# KW2CPU_PCB.net
KiCad netlist of a schematic drawn in EAGLE
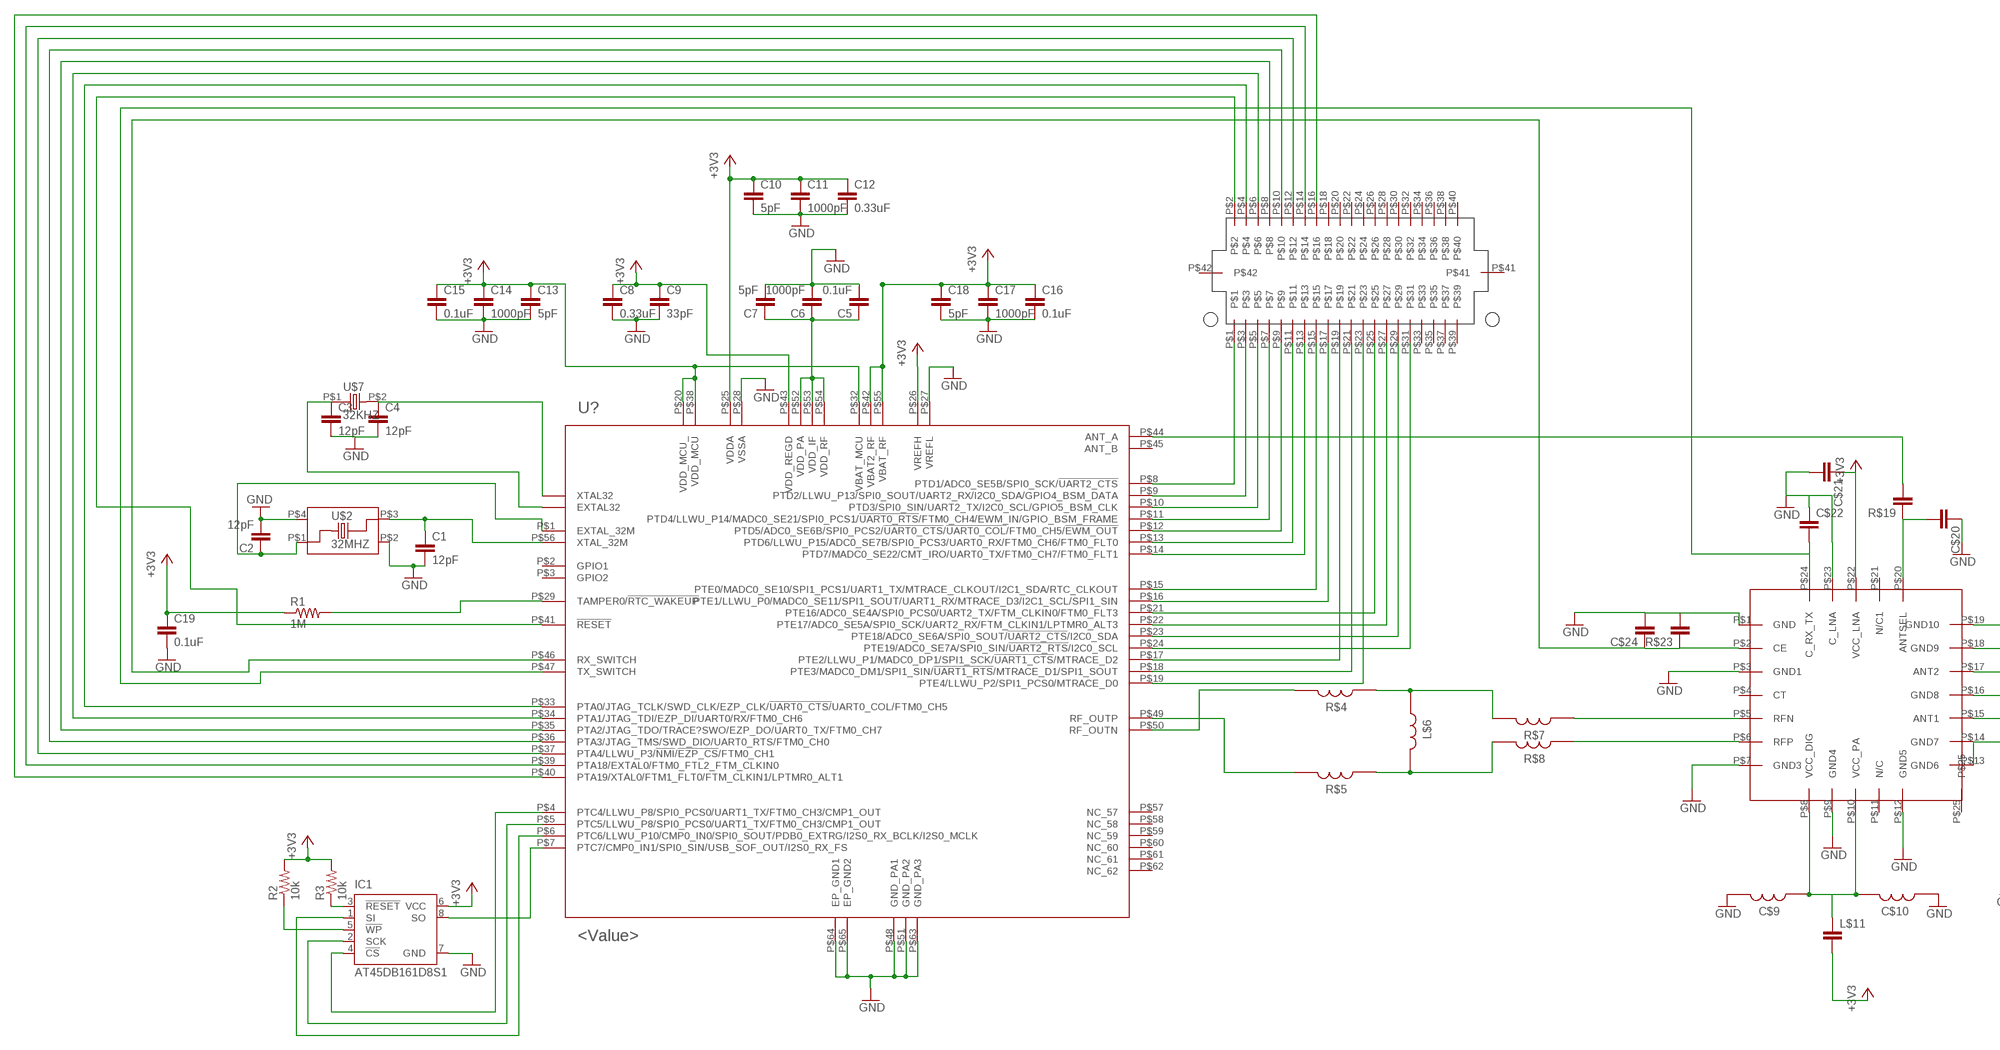
[diagram p0: schematic, sheet 1, part 1 of 2]
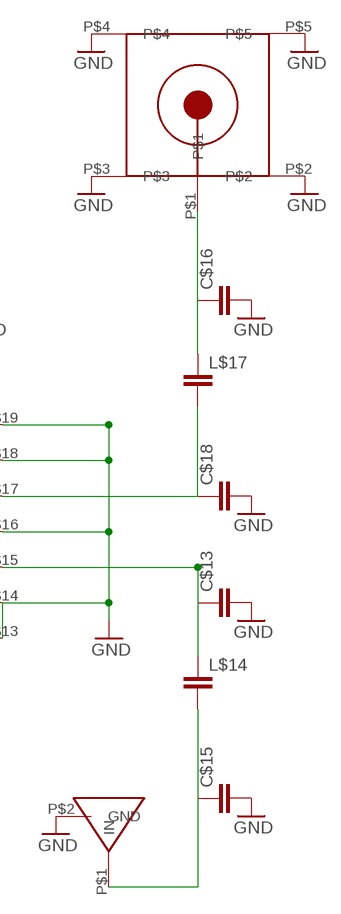
[diagram p1: schematic, sheet 1, part 2 of 2]

(export (version "E")
  (design (tool "Eeschema 10.0.6"))
  (components
    (comp (ref "C$9")
      (value "RF-L")
      (footprint "eagle-import:RF-L0201")
      (libsource (lib "eagle-import") (part "RF-L"))
    )
    (comp (ref "C$10")
      (value "RF-L")
      (footprint "eagle-import:RF-L0201")
      (libsource (lib "eagle-import") (part "RF-L"))
    )
    (comp (ref "C$13")
      (value "RF-C")
      (footprint "eagle-import:RFMD0402")
      (libsource (lib "eagle-import") (part "RF-C"))
    )
    (comp (ref "C$15")
      (value "RF-C")
      (footprint "eagle-import:RFMD0402")
      (libsource (lib "eagle-import") (part "RF-C"))
    )
    (comp (ref "C$16")
      (value "RF-C")
      (footprint "eagle-import:RFMD0402")
      (libsource (lib "eagle-import") (part "RF-C"))
    )
    (comp (ref "C$18")
      (value "RF-C")
      (footprint "eagle-import:RFMD0402")
      (libsource (lib "eagle-import") (part "RF-C"))
    )
    (comp (ref "C$20")
      (value "RF-C")
      (footprint "eagle-import:RFMD0402")
      (libsource (lib "eagle-import") (part "RF-C"))
    )
    (comp (ref "C$21")
      (value "RF-C")
      (footprint "eagle-import:RFMD0402")
      (libsource (lib "eagle-import") (part "RF-C"))
    )
    (comp (ref "C$22")
      (value "RF-C")
      (footprint "eagle-import:RFMD0402")
      (libsource (lib "eagle-import") (part "RF-C"))
    )
    (comp (ref "C$24")
      (value "RF-C")
      (footprint "eagle-import:RFMD0402")
      (libsource (lib "eagle-import") (part "RF-C"))
    )
    (comp (ref "C1")
      (value "12pF")
      (footprint "eagle-import:C0402")
      (libsource (lib "eagle-import") (part "RF-C0402"))
    )
    (comp (ref "C2")
      (value "12pF")
      (footprint "eagle-import:C0402")
      (libsource (lib "eagle-import") (part "RF-C0402"))
    )
    (comp (ref "C3")
      (value "12pF")
      (footprint "eagle-import:C0402")
      (libsource (lib "eagle-import") (part "RF-C0402"))
    )
    (comp (ref "C4")
      (value "12pF")
      (footprint "eagle-import:C0402")
      (libsource (lib "eagle-import") (part "RF-C0402"))
    )
    (comp (ref "C5")
      (value "0.1uF")
      (footprint "eagle-import:C0402")
      (libsource (lib "eagle-import") (part "RF-C0402"))
    )
    (comp (ref "C6")
      (value "1000pF")
      (footprint "eagle-import:C0402")
      (libsource (lib "eagle-import") (part "RF-C0402"))
    )
    (comp (ref "C7")
      (value "5pF")
      (footprint "eagle-import:C0402")
      (libsource (lib "eagle-import") (part "RF-C0402"))
    )
    (comp (ref "C8")
      (value "0.33uF")
      (footprint "eagle-import:C0402")
      (libsource (lib "eagle-import") (part "RF-C0402"))
    )
    (comp (ref "C9")
      (value "33pF")
      (footprint "eagle-import:C0402")
      (libsource (lib "eagle-import") (part "RF-C0402"))
    )
    (comp (ref "C10")
      (value "5pF")
      (footprint "eagle-import:C0402")
      (libsource (lib "eagle-import") (part "RF-C0402"))
    )
    (comp (ref "C11")
      (value "1000pF")
      (footprint "eagle-import:C0402")
      (libsource (lib "eagle-import") (part "RF-C0402"))
    )
    (comp (ref "C12")
      (value "0.33uF")
      (footprint "eagle-import:C0402")
      (libsource (lib "eagle-import") (part "RF-C0402"))
    )
    (comp (ref "C13")
      (value "5pF")
      (footprint "eagle-import:C0402")
      (libsource (lib "eagle-import") (part "RF-C0402"))
    )
    (comp (ref "C14")
      (value "1000pF")
      (footprint "eagle-import:C0402")
      (libsource (lib "eagle-import") (part "RF-C0402"))
    )
    (comp (ref "C15")
      (value "0.1uF")
      (footprint "eagle-import:C0402")
      (libsource (lib "eagle-import") (part "RF-C0402"))
    )
    (comp (ref "C16")
      (value "0.1uF")
      (footprint "eagle-import:C0402")
      (libsource (lib "eagle-import") (part "RF-C0402"))
    )
    (comp (ref "C17")
      (value "1000pF")
      (footprint "eagle-import:C0402")
      (libsource (lib "eagle-import") (part "RF-C0402"))
    )
    (comp (ref "C18")
      (value "5pF")
      (footprint "eagle-import:C0402")
      (libsource (lib "eagle-import") (part "RF-C0402"))
    )
    (comp (ref "C19")
      (value "0.1uF")
      (footprint "eagle-import:C0402")
      (libsource (lib "eagle-import") (part "RF-C0402"))
    )
    (comp (ref "IC1")
      (value "AT45DB161D8S1")
      (footprint "eagle-import:8S1")
      (libsource (lib "eagle-import") (part "AT45DB161D8S1"))
    )
    (comp (ref "L$6")
      (value "RF-L")
      (footprint "eagle-import:RF-L0201")
      (libsource (lib "eagle-import") (part "RF-L"))
    )
    (comp (ref "L$11")
      (value "RF-C")
      (footprint "eagle-import:RFMD0402")
      (libsource (lib "eagle-import") (part "RF-C"))
    )
    (comp (ref "L$14")
      (value "RF-C")
      (footprint "eagle-import:RFMD0402")
      (libsource (lib "eagle-import") (part "RF-C"))
    )
    (comp (ref "L$17")
      (value "RF-C")
      (footprint "eagle-import:RFMD0402")
      (libsource (lib "eagle-import") (part "RF-C"))
    )
    (comp (ref "R$4")
      (value "RF-L")
      (footprint "eagle-import:RF-L0201")
      (libsource (lib "eagle-import") (part "RF-L"))
    )
    (comp (ref "R$5")
      (value "RF-L")
      (footprint "eagle-import:RF-L0201")
      (libsource (lib "eagle-import") (part "RF-L"))
    )
    (comp (ref "R$7")
      (value "RF-L")
      (footprint "eagle-import:RF-L0201")
      (libsource (lib "eagle-import") (part "RF-L"))
    )
    (comp (ref "R$8")
      (value "RF-L")
      (footprint "eagle-import:RF-L0201")
      (libsource (lib "eagle-import") (part "RF-L"))
    )
    (comp (ref "R$19")
      (value "RF-C")
      (footprint "eagle-import:RFMD0402")
      (libsource (lib "eagle-import") (part "RF-C"))
    )
    (comp (ref "R$23")
      (value "RF-C")
      (footprint "eagle-import:RFMD0402")
      (libsource (lib "eagle-import") (part "RF-C"))
    )
    (comp (ref "R1")
      (value "1M")
      (footprint "eagle-import:RF-R0402")
      (libsource (lib "eagle-import") (part "RF-R0402"))
    )
    (comp (ref "R2")
      (value "10k")
      (footprint "eagle-import:RF-R0402")
      (libsource (lib "eagle-import") (part "RF-R0402"))
    )
    (comp (ref "R3")
      (value "10k")
      (footprint "eagle-import:RF-R0402")
      (libsource (lib "eagle-import") (part "RF-R0402"))
    )
    (comp (ref "U$1")
      (value "MKW21D")
      (footprint "eagle-import:LGA63")
      (libsource (lib "eagle-import") (part "MKW21D"))
    )
    (comp (ref "U$2")
      (value "32MHZ")
      (footprint "eagle-import:32MHZSMD")
      (libsource (lib "eagle-import") (part "32MHZ"))
    )
    (comp (ref "U$3")
      (value "RF6555")
      (footprint "eagle-import:RF6555")
      (libsource (lib "eagle-import") (part "RF6555"))
    )
    (comp (ref "U$4")
      (value "F-ANTENNA")
      (footprint "eagle-import:F_ANT_RFMD")
      (libsource (lib "eagle-import") (part "F-ANTENNA"))
    )
    (comp (ref "U$5")
      (value "MMCX_VERT")
      (footprint "eagle-import:MMCX_VERT")
      (libsource (lib "eagle-import") (part "MMCX_VERT"))
    )
    (comp (ref "U$6")
      (value "DF12_M")
      (footprint "eagle-import:DF12_M")
      (libsource (lib "eagle-import") (part "DF12_M"))
    )
    (comp (ref "U$7")
      (value "32KHZ")
      (footprint "eagle-import:32KHZSMD")
      (libsource (lib "eagle-import") (part "32KHZ"))
    )
  )
  (nets
    (net (code "1") (name "+3V3") (class "Default")
      (node (ref "C$21") (pin "P$1") (pinfunction "1_P$1") (pintype "passive"))
      (node (ref "C10") (pin "1") (pinfunction "1_1") (pintype "passive"))
      (node (ref "C11") (pin "1") (pinfunction "1_1") (pintype "passive"))
      (node (ref "C12") (pin "1") (pinfunction "1_1") (pintype "passive"))
      (node (ref "C13") (pin "1") (pinfunction "1_1") (pintype "passive"))
      (node (ref "C14") (pin "1") (pinfunction "1_1") (pintype "passive"))
      (node (ref "C15") (pin "1") (pinfunction "1_1") (pintype "passive"))
      (node (ref "C16") (pin "1") (pinfunction "1_1") (pintype "passive"))
      (node (ref "C17") (pin "1") (pinfunction "1_1") (pintype "passive"))
      (node (ref "C18") (pin "1") (pinfunction "1_1") (pintype "passive"))
      (node (ref "C19") (pin "1") (pinfunction "1_1") (pintype "passive"))
      (node (ref "C8") (pin "1") (pinfunction "1_1") (pintype "passive"))
      (node (ref "C9") (pin "1") (pinfunction "1_1") (pintype "passive"))
      (node (ref "IC1") (pin "6") (pinfunction "VCC_6") (pintype "power_in"))
      (node (ref "L$11") (pin "P$2") (pinfunction "2_P$2") (pintype "passive"))
      (node (ref "R1") (pin "1") (pinfunction "1_1") (pintype "passive"))
      (node (ref "R2") (pin "2") (pinfunction "2_2") (pintype "passive"))
      (node (ref "R3") (pin "2") (pinfunction "2_2") (pintype "passive"))
      (node (ref "U$1") (pin "P$20") (pinfunction "VDD_MCU__P$20") (pintype "bidirectional"))
      (node (ref "U$1") (pin "P$25") (pinfunction "VDDA_P$25") (pintype "bidirectional"))
      (node (ref "U$1") (pin "P$26") (pinfunction "VREFH_P$26") (pintype "bidirectional"))
      (node (ref "U$1") (pin "P$32") (pinfunction "VBAT_MCU_P$32") (pintype "bidirectional"))
      (node (ref "U$1") (pin "P$38") (pinfunction "VDD_MCU_P$38") (pintype "bidirectional"))
      (node (ref "U$1") (pin "P$42") (pinfunction "VBAT2_RF_P$42") (pintype "bidirectional"))
      (node (ref "U$1") (pin "P$43") (pinfunction "VDD_REGD_P$43") (pintype "bidirectional"))
      (node (ref "U$1") (pin "P$55") (pinfunction "VBAT_RF_P$55") (pintype "bidirectional"))
      (node (ref "U$3") (pin "P$22") (pinfunction "VCC_LNA_P$22") (pintype "bidirectional"))
    )
    (net (code "2") (name "GND") (class "Default")
      (node (ref "C$10") (pin "P$2") (pinfunction "2_P$2") (pintype "bidirectional"))
      (node (ref "C$13") (pin "P$2") (pinfunction "2_P$2") (pintype "passive"))
      (node (ref "C$15") (pin "P$2") (pinfunction "2_P$2") (pintype "passive"))
      (node (ref "C$16") (pin "P$2") (pinfunction "2_P$2") (pintype "passive"))
      (node (ref "C$18") (pin "P$2") (pinfunction "2_P$2") (pintype "passive"))
      (node (ref "C$20") (pin "P$1") (pinfunction "1_P$1") (pintype "passive"))
      (node (ref "C$21") (pin "P$2") (pinfunction "2_P$2") (pintype "passive"))
      (node (ref "C$22") (pin "P$1") (pinfunction "1_P$1") (pintype "passive"))
      (node (ref "C$24") (pin "P$2") (pinfunction "2_P$2") (pintype "passive"))
      (node (ref "C$9") (pin "P$1") (pinfunction "1_P$1") (pintype "bidirectional"))
      (node (ref "C1") (pin "2") (pinfunction "2_2") (pintype "passive"))
      (node (ref "C10") (pin "2") (pinfunction "2_2") (pintype "passive"))
      (node (ref "C11") (pin "2") (pinfunction "2_2") (pintype "passive"))
      (node (ref "C12") (pin "2") (pinfunction "2_2") (pintype "passive"))
      (node (ref "C13") (pin "2") (pinfunction "2_2") (pintype "passive"))
      (node (ref "C14") (pin "2") (pinfunction "2_2") (pintype "passive"))
      (node (ref "C15") (pin "2") (pinfunction "2_2") (pintype "passive"))
      (node (ref "C16") (pin "2") (pinfunction "2_2") (pintype "passive"))
      (node (ref "C17") (pin "2") (pinfunction "2_2") (pintype "passive"))
      (node (ref "C18") (pin "2") (pinfunction "2_2") (pintype "passive"))
      (node (ref "C19") (pin "2") (pinfunction "2_2") (pintype "passive"))
      (node (ref "C2") (pin "2") (pinfunction "2_2") (pintype "passive"))
      (node (ref "C3") (pin "2") (pinfunction "2_2") (pintype "passive"))
      (node (ref "C4") (pin "2") (pinfunction "2_2") (pintype "passive"))
      (node (ref "C5") (pin "2") (pinfunction "2_2") (pintype "passive"))
      (node (ref "C6") (pin "2") (pinfunction "2_2") (pintype "passive"))
      (node (ref "C7") (pin "2") (pinfunction "2_2") (pintype "passive"))
      (node (ref "C8") (pin "2") (pinfunction "2_2") (pintype "passive"))
      (node (ref "C9") (pin "2") (pinfunction "2_2") (pintype "passive"))
      (node (ref "IC1") (pin "7") (pinfunction "GND_7") (pintype "power_in"))
      (node (ref "U$1") (pin "P$27") (pinfunction "VREFL_P$27") (pintype "bidirectional"))
      (node (ref "U$1") (pin "P$28") (pinfunction "VSSA_P$28") (pintype "bidirectional"))
      (node (ref "U$1") (pin "P$48") (pinfunction "GND_PA1_P$48") (pintype "bidirectional"))
      (node (ref "U$1") (pin "P$51") (pinfunction "GND_PA2_P$51") (pintype "bidirectional"))
      (node (ref "U$1") (pin "P$63") (pinfunction "GND_PA3_P$63") (pintype "bidirectional"))
      (node (ref "U$1") (pin "P$64") (pinfunction "EP_GND1_P$64") (pintype "bidirectional"))
      (node (ref "U$1") (pin "P$65") (pinfunction "EP_GND2_P$65") (pintype "bidirectional"))
      (node (ref "U$2") (pin "P$2") (pinfunction "P$2_P$2") (pintype "power_in"))
      (node (ref "U$2") (pin "P$4") (pinfunction "P$4_P$4") (pintype "bidirectional"))
      (node (ref "U$3") (pin "P$1") (pinfunction "GND_P$1") (pintype "bidirectional"))
      (node (ref "U$3") (pin "P$12") (pinfunction "GND5_P$12") (pintype "bidirectional"))
      (node (ref "U$3") (pin "P$13") (pinfunction "GND6_P$13") (pintype "bidirectional"))
      (node (ref "U$3") (pin "P$14") (pinfunction "GND7_P$14") (pintype "bidirectional"))
      (node (ref "U$3") (pin "P$16") (pinfunction "GND8_P$16") (pintype "bidirectional"))
      (node (ref "U$3") (pin "P$18") (pinfunction "GND9_P$18") (pintype "bidirectional"))
      (node (ref "U$3") (pin "P$19") (pinfunction "GND10_P$19") (pintype "bidirectional"))
      (node (ref "U$3") (pin "P$23") (pinfunction "C_LNA_P$23") (pintype "bidirectional"))
      (node (ref "U$3") (pin "P$3") (pinfunction "GND1_P$3") (pintype "bidirectional"))
      (node (ref "U$3") (pin "P$7") (pinfunction "GND3_P$7") (pintype "bidirectional"))
      (node (ref "U$3") (pin "P$9") (pinfunction "GND4_P$9") (pintype "bidirectional"))
      (node (ref "U$4") (pin "P$2") (pinfunction "GND_P$2") (pintype "bidirectional"))
      (node (ref "U$5") (pin "P$2") (pinfunction "P$2_P$2") (pintype "bidirectional"))
      (node (ref "U$5") (pin "P$3") (pinfunction "P$3_P$3") (pintype "bidirectional"))
      (node (ref "U$5") (pin "P$4") (pinfunction "P$4_P$4") (pintype "bidirectional"))
      (node (ref "U$5") (pin "P$5") (pinfunction "P$5_P$5") (pintype "bidirectional"))
    )
    (net (code "3") (name "Net-(C$10-1)") (class "Default")
      (node (ref "C$10") (pin "P$1") (pinfunction "1_P$1") (pintype "bidirectional"))
      (node (ref "C$9") (pin "P$2") (pinfunction "2_P$2") (pintype "bidirectional"))
      (node (ref "L$11") (pin "P$1") (pinfunction "1_P$1") (pintype "passive"))
      (node (ref "U$3") (pin "P$10") (pinfunction "VCC_PA_P$10") (pintype "bidirectional"))
      (node (ref "U$3") (pin "P$8") (pinfunction "VCC_DIG_P$8") (pintype "bidirectional"))
    )
    (net (code "4") (name "Net-(C$13-1)") (class "Default")
      (node (ref "C$13") (pin "P$1") (pinfunction "1_P$1") (pintype "passive"))
      (node (ref "L$14") (pin "P$1") (pinfunction "1_P$1") (pintype "passive"))
      (node (ref "U$3") (pin "P$15") (pinfunction "ANT1_P$15") (pintype "bidirectional"))
    )
    (net (code "5") (name "Net-(C$15-1)") (class "Default")
      (node (ref "C$15") (pin "P$1") (pinfunction "1_P$1") (pintype "passive"))
      (node (ref "L$14") (pin "P$2") (pinfunction "2_P$2") (pintype "passive"))
      (node (ref "U$4") (pin "P$1") (pinfunction "IN_P$1") (pintype "bidirectional"))
    )
    (net (code "6") (name "Net-(C$16-1)") (class "Default")
      (node (ref "C$16") (pin "P$1") (pinfunction "1_P$1") (pintype "passive"))
      (node (ref "L$17") (pin "P$1") (pinfunction "1_P$1") (pintype "passive"))
      (node (ref "U$5") (pin "P$1") (pinfunction "P$1_P$1") (pintype "bidirectional"))
    )
    (net (code "7") (name "Net-(C$18-1)") (class "Default")
      (node (ref "C$18") (pin "P$1") (pinfunction "1_P$1") (pintype "passive"))
      (node (ref "L$17") (pin "P$2") (pinfunction "2_P$2") (pintype "passive"))
      (node (ref "U$3") (pin "P$17") (pinfunction "ANT2_P$17") (pintype "bidirectional"))
    )
    (net (code "8") (name "Net-(C$20-2)") (class "Default")
      (node (ref "C$20") (pin "P$2") (pinfunction "2_P$2") (pintype "passive"))
      (node (ref "R$19") (pin "P$1") (pinfunction "1_P$1") (pintype "passive"))
      (node (ref "U$3") (pin "P$20") (pinfunction "ANTSEL_P$20") (pintype "bidirectional"))
    )
    (net (code "9") (name "Net-(C$22-2)") (class "Default")
      (node (ref "C$22") (pin "P$2") (pinfunction "2_P$2") (pintype "passive"))
      (node (ref "U$1") (pin "P$47") (pinfunction "TX_SWITCH_P$47") (pintype "bidirectional"))
      (node (ref "U$3") (pin "P$24") (pinfunction "C_RX_TX_P$24") (pintype "bidirectional"))
    )
    (net (code "10") (name "Net-(C$24-1)") (class "Default")
      (node (ref "C$24") (pin "P$1") (pinfunction "1_P$1") (pintype "passive"))
      (node (ref "R$23") (pin "P$1") (pinfunction "1_P$1") (pintype "passive"))
      (node (ref "U$1") (pin "P$46") (pinfunction "RX_SWITCH_P$46") (pintype "bidirectional"))
      (node (ref "U$3") (pin "P$2") (pinfunction "CE_P$2") (pintype "bidirectional"))
    )
    (net (code "11") (name "Net-(IC1-SCK)") (class "Default")
      (node (ref "IC1") (pin "2") (pinfunction "SCK_2") (pintype "input"))
      (node (ref "U$1") (pin "P$5") (pinfunction "PTC5/LLWU_P8/SPI0_PCS0/UART1_TX/FTM0_CH3/CMP1_OUT_P$5") (pintype "bidirectional"))
    )
    (net (code "12") (name "Net-(IC1-SI)") (class "Default")
      (node (ref "IC1") (pin "1") (pinfunction "SI_1") (pintype "input"))
      (node (ref "U$1") (pin "P$6") (pinfunction "PTC6/LLWU_P10/CMP0_IN0/SPI0_SOUT/PDB0_EXTRG/I2S0_RX_BCLK/I2S0_MCLK_P$6") (pintype "bidirectional"))
    )
    (net (code "13") (name "Net-(IC1-SO)") (class "Default")
      (node (ref "IC1") (pin "8") (pinfunction "SO_8") (pintype "output"))
      (node (ref "U$1") (pin "P$7") (pinfunction "PTC7/CMP0_IN1/SPI0_SIN/USB_SOF_OUT/I2S0_RX_FS_P$7") (pintype "bidirectional"))
    )
    (net (code "14") (name "Net-(IC1-~{CS})") (class "Default")
      (node (ref "IC1") (pin "4") (pinfunction "~{CS}_4") (pintype "input"))
      (node (ref "U$1") (pin "P$4") (pinfunction "PTC4/LLWU_P8/SPI0_PCS0/UART1_TX/FTM0_CH3/CMP1_OUT_P$4") (pintype "bidirectional"))
    )
    (net (code "15") (name "Net-(IC1-~{RESET})") (class "Default")
      (node (ref "IC1") (pin "3") (pinfunction "~{RESET}_3") (pintype "input"))
      (node (ref "R3") (pin "1") (pinfunction "1_1") (pintype "passive"))
    )
    (net (code "16") (name "Net-(IC1-~{WP})") (class "Default")
      (node (ref "IC1") (pin "5") (pinfunction "~{WP}_5") (pintype "input"))
      (node (ref "R2") (pin "1") (pinfunction "1_1") (pintype "passive"))
    )
    (net (code "17") (name "Net-(L$6-1)") (class "Default")
      (node (ref "L$6") (pin "P$1") (pinfunction "1_P$1") (pintype "bidirectional"))
      (node (ref "R$5") (pin "P$2") (pinfunction "2_P$2") (pintype "bidirectional"))
      (node (ref "R$8") (pin "P$1") (pinfunction "1_P$1") (pintype "bidirectional"))
    )
    (net (code "18") (name "Net-(L$6-2)") (class "Default")
      (node (ref "L$6") (pin "P$2") (pinfunction "2_P$2") (pintype "bidirectional"))
      (node (ref "R$4") (pin "P$2") (pinfunction "2_P$2") (pintype "bidirectional"))
      (node (ref "R$7") (pin "P$1") (pinfunction "1_P$1") (pintype "bidirectional"))
    )
    (net (code "19") (name "Net-(R$4-1)") (class "Default")
      (node (ref "R$4") (pin "P$1") (pinfunction "1_P$1") (pintype "bidirectional"))
      (node (ref "U$1") (pin "P$50") (pinfunction "RF_OUTN_P$50") (pintype "bidirectional"))
    )
    (net (code "20") (name "Net-(R$5-1)") (class "Default")
      (node (ref "R$5") (pin "P$1") (pinfunction "1_P$1") (pintype "bidirectional"))
      (node (ref "U$1") (pin "P$49") (pinfunction "RF_OUTP_P$49") (pintype "bidirectional"))
    )
    (net (code "21") (name "Net-(R$7-2)") (class "Default")
      (node (ref "R$7") (pin "P$2") (pinfunction "2_P$2") (pintype "bidirectional"))
      (node (ref "U$3") (pin "P$5") (pinfunction "RFN_P$5") (pintype "bidirectional"))
    )
    (net (code "22") (name "Net-(R$8-2)") (class "Default")
      (node (ref "R$8") (pin "P$2") (pinfunction "2_P$2") (pintype "bidirectional"))
      (node (ref "U$3") (pin "P$6") (pinfunction "RFP_P$6") (pintype "bidirectional"))
    )
    (net (code "23") (name "Net-(R$19-2)") (class "Default")
      (node (ref "R$19") (pin "P$2") (pinfunction "2_P$2") (pintype "passive"))
      (node (ref "U$1") (pin "P$44") (pinfunction "ANT_A_P$44") (pintype "bidirectional"))
    )
    (net (code "24") (name "Net-(U$1-EXTAL32)") (class "Default")
      (node (ref "C3") (pin "1") (pinfunction "1_1") (pintype "passive"))
      (node (ref "U$1") (pin "P$31") (pinfunction "EXTAL32_P$31") (pintype "bidirectional"))
      (node (ref "U$7") (pin "P$1") (pinfunction "1_P$1") (pintype "passive"))
    )
    (net (code "25") (name "Net-(U$1-EXTAL_32M)") (class "Default")
      (node (ref "C2") (pin "1") (pinfunction "1_1") (pintype "passive"))
      (node (ref "U$1") (pin "P$1") (pinfunction "EXTAL_32M_P$1") (pintype "bidirectional"))
      (node (ref "U$2") (pin "P$1") (pinfunction "P$1_P$1") (pintype "passive"))
    )
    (net (code "26") (name "Net-(U$1-PTA0{slash}JTAG_TCLK{slash}SWD_CLK{slash}EZP_CLK{slash}~{UART0_CTS{slash}}UART0_COL{slash}FTM0_CH5)") (class "Default")
      (node (ref "U$1") (pin "P$33") (pinfunction "PTA0/JTAG_TCLK/SWD_CLK/EZP_CLK/~{UART0_CTS/}UART0_COL/FTM0_CH5_P$33") (pintype "bidirectional"))
      (node (ref "U$6") (pin "P$4") (pinfunction "P$4_P$4") (pintype "bidirectional"))
    )
    (net (code "27") (name "Net-(U$1-PTA1{slash}JTAG_TDI{slash}EZP_DI{slash}UART0{slash}RX{slash}FTM0_CH6)") (class "Default")
      (node (ref "U$1") (pin "P$34") (pinfunction "PTA1/JTAG_TDI/EZP_DI/UART0/RX/FTM0_CH6_P$34") (pintype "bidirectional"))
      (node (ref "U$6") (pin "P$6") (pinfunction "P$6_P$6") (pintype "bidirectional"))
    )
    (net (code "28") (name "Net-(U$1-PTA2{slash}JTAG_TDO{slash}TRACE?SWO{slash}EZP_DO{slash}UART0_TX{slash}FTM0_CH7)") (class "Default")
      (node (ref "U$1") (pin "P$35") (pinfunction "PTA2/JTAG_TDO/TRACE?SWO/EZP_DO/UART0_TX/FTM0_CH7_P$35") (pintype "bidirectional"))
      (node (ref "U$6") (pin "P$8") (pinfunction "P$8_P$8") (pintype "bidirectional"))
    )
    (net (code "29") (name "Net-(U$1-PTA3{slash}JTAG_TMS{slash}SWD_DIO{slash}UART0_RTS{slash}FTM0_CH0)") (class "Default")
      (node (ref "U$1") (pin "P$36") (pinfunction "PTA3/JTAG_TMS/SWD_DIO/UART0_RTS/FTM0_CH0_P$36") (pintype "bidirectional"))
      (node (ref "U$6") (pin "P$10") (pinfunction "P$10_P$10") (pintype "bidirectional"))
    )
    (net (code "30") (name "Net-(U$1-PTA4{slash}LLWU_P3{slash}~{NMI}{slash}~{EZP_CS}{slash}FTM0_CH1)") (class "Default")
      (node (ref "U$1") (pin "P$37") (pinfunction "PTA4/LLWU_P3/~{NMI}/~{EZP_CS}/FTM0_CH1_P$37") (pintype "bidirectional"))
      (node (ref "U$6") (pin "P$12") (pinfunction "P$12_P$12") (pintype "bidirectional"))
    )
    (net (code "31") (name "Net-(U$1-PTA18{slash}EXTAL0{slash}FTM0_FTL2_FTM_CLKIN0)") (class "Default")
      (node (ref "U$1") (pin "P$39") (pinfunction "PTA18/EXTAL0/FTM0_FTL2_FTM_CLKIN0_P$39") (pintype "bidirectional"))
      (node (ref "U$6") (pin "P$14") (pinfunction "P$14_P$14") (pintype "bidirectional"))
    )
    (net (code "32") (name "Net-(U$1-PTA19{slash}XTAL0{slash}FTM1_FLT0{slash}FTM_CLKIN1{slash}LPTMR0_ALT1)") (class "Default")
      (node (ref "U$1") (pin "P$40") (pinfunction "PTA19/XTAL0/FTM1_FLT0/FTM_CLKIN1/LPTMR0_ALT1_P$40") (pintype "bidirectional"))
      (node (ref "U$6") (pin "P$16") (pinfunction "P$16_P$16") (pintype "bidirectional"))
    )
    (net (code "33") (name "Net-(U$1-PTD1{slash}ADC0_SE5B{slash}SPI0_SCK{slash}~{UART2_CTS})") (class "Default")
      (node (ref "U$1") (pin "P$8") (pinfunction "PTD1/ADC0_SE5B/SPI0_SCK/~{UART2_CTS}_P$8") (pintype "bidirectional"))
      (node (ref "U$6") (pin "P$1") (pinfunction "P$1_P$1") (pintype "bidirectional"))
    )
    (net (code "34") (name "Net-(U$1-PTD2{slash}LLWU_P13{slash}SPI0_SOUT{slash}UART2_RX{slash}I2C0_SDA{slash}GPIO4_BSM_DATA)") (class "Default")
      (node (ref "U$1") (pin "P$9") (pinfunction "PTD2/LLWU_P13/SPI0_SOUT/UART2_RX/I2C0_SDA/GPIO4_BSM_DATA_P$9") (pintype "bidirectional"))
      (node (ref "U$6") (pin "P$3") (pinfunction "P$3_P$3") (pintype "bidirectional"))
    )
    (net (code "35") (name "Net-(U$1-PTD3{slash}SPI0_SIN{slash}UART2_TX{slash}I2C0_SCL{slash}GPIO5_BSM_CLK)") (class "Default")
      (node (ref "U$1") (pin "P$10") (pinfunction "PTD3/SPI0_SIN/UART2_TX/I2C0_SCL/GPIO5_BSM_CLK_P$10") (pintype "bidirectional"))
      (node (ref "U$6") (pin "P$5") (pinfunction "P$5_P$5") (pintype "bidirectional"))
    )
    (net (code "36") (name "Net-(U$1-PTD4{slash}LLWU_P14{slash}MADC0_SE21{slash}SPI0_PCS1{slash}~{UART0_RTS}{slash}FTM0_CH4{slash}EWM_IN{slash}GPIO_BSM_FRAME)") (class "Default")
      (node (ref "U$1") (pin "P$11") (pinfunction "PTD4/LLWU_P14/MADC0_SE21/SPI0_PCS1/~{UART0_RTS}/FTM0_CH4/EWM_IN/GPIO_BSM_FRAME_P$11") (pintype "bidirectional"))
      (node (ref "U$6") (pin "P$7") (pinfunction "P$7_P$7") (pintype "bidirectional"))
    )
    (net (code "37") (name "Net-(U$1-PTD5{slash}ADC0_SE6B{slash}SPI0_PCS2{slash}~{UART0_CTS}{slash}~{UART0_COL}{slash}FTM0_CH5{slash}~{EWM_OUT})") (class "Default")
      (node (ref "U$1") (pin "P$12") (pinfunction "PTD5/ADC0_SE6B/SPI0_PCS2/~{UART0_CTS}/~{UART0_COL}/FTM0_CH5/~{EWM_OUT}_P$12") (pintype "bidirectional"))
      (node (ref "U$6") (pin "P$9") (pinfunction "P$9_P$9") (pintype "bidirectional"))
    )
    (net (code "38") (name "Net-(U$1-PTD6{slash}LLWU_P15{slash}ADC0_SE7B{slash}SPI0_PCS3{slash}UART0_RX{slash}FTM0_CH6{slash}FTM0_FLT0)") (class "Default")
      (node (ref "U$1") (pin "P$13") (pinfunction "PTD6/LLWU_P15/ADC0_SE7B/SPI0_PCS3/UART0_RX/FTM0_CH6/FTM0_FLT0_P$13") (pintype "bidirectional"))
      (node (ref "U$6") (pin "P$11") (pinfunction "P$11_P$11") (pintype "bidirectional"))
    )
    (net (code "39") (name "Net-(U$1-PTD7{slash}MADC0_SE22{slash}CMT_IRO{slash}UART0_TX{slash}FTM0_CH7{slash}FTM0_FLT1)") (class "Default")
      (node (ref "U$1") (pin "P$14") (pinfunction "PTD7/MADC0_SE22/CMT_IRO/UART0_TX/FTM0_CH7/FTM0_FLT1_P$14") (pintype "bidirectional"))
      (node (ref "U$6") (pin "P$13") (pinfunction "P$13_P$13") (pintype "bidirectional"))
    )
    (net (code "40") (name "Net-(U$1-PTE0{slash}MADC0_SE10{slash}SPI1_PCS1{slash}UART1_TX{slash}MTRACE_CLKOUT{slash}I2C1_SDA{slash}RTC_CLKOUT)") (class "Default")
      (node (ref "U$1") (pin "P$15") (pinfunction "PTE0/MADC0_SE10/SPI1_PCS1/UART1_TX/MTRACE_CLKOUT/I2C1_SDA/RTC_CLKOUT_P$15") (pintype "bidirectional"))
      (node (ref "U$6") (pin "P$15") (pinfunction "P$15_P$15") (pintype "bidirectional"))
    )
    (net (code "41") (name "Net-(U$1-PTE1{slash}LLWU_P0{slash}MADC0_SE11{slash}SPI1_SOUT{slash}UART1_RX{slash}MTRACE_D3{slash}I2C1_SCL{slash}SPI1_SIN)") (class "Default")
      (node (ref "U$1") (pin "P$16") (pinfunction "PTE1/LLWU_P0/MADC0_SE11/SPI1_SOUT/UART1_RX/MTRACE_D3/I2C1_SCL/SPI1_SIN_P$16") (pintype "bidirectional"))
      (node (ref "U$6") (pin "P$17") (pinfunction "P$17_P$17") (pintype "bidirectional"))
    )
    (net (code "42") (name "Net-(U$1-PTE2{slash}LLWU_P1{slash}MADC0_DP1{slash}SPI1_SCK{slash}~{UART1_CTS}{slash}MTRACE_D2)") (class "Default")
      (node (ref "U$1") (pin "P$17") (pinfunction "PTE2/LLWU_P1/MADC0_DP1/SPI1_SCK/~{UART1_CTS}/MTRACE_D2_P$17") (pintype "bidirectional"))
      (node (ref "U$6") (pin "P$19") (pinfunction "P$19_P$19") (pintype "bidirectional"))
    )
    (net (code "43") (name "Net-(U$1-PTE3{slash}MADC0_DM1{slash}SPI1_SIN{slash}~{UART1_RTS}{slash}MTRACE_D1{slash}SPI1_SOUT)") (class "Default")
      (node (ref "U$1") (pin "P$18") (pinfunction "PTE3/MADC0_DM1/SPI1_SIN/~{UART1_RTS}/MTRACE_D1/SPI1_SOUT_P$18") (pintype "bidirectional"))
      (node (ref "U$6") (pin "P$21") (pinfunction "P$21_P$21") (pintype "bidirectional"))
    )
    (net (code "44") (name "Net-(U$1-PTE4{slash}LLWU_P2{slash}SPI1_PCS0{slash}MTRACE_D0)") (class "Default")
      (node (ref "U$1") (pin "P$19") (pinfunction "PTE4/LLWU_P2/SPI1_PCS0/MTRACE_D0_P$19") (pintype "bidirectional"))
      (node (ref "U$6") (pin "P$23") (pinfunction "P$23_P$23") (pintype "bidirectional"))
    )
    (net (code "45") (name "Net-(U$1-PTE16{slash}ADC0_SE4A{slash}SPI0_PCS0{slash}UART2_TX{slash}FTM_CLKIN0{slash}FTM0_FLT3)") (class "Default")
      (node (ref "U$1") (pin "P$21") (pinfunction "PTE16/ADC0_SE4A/SPI0_PCS0/UART2_TX/FTM_CLKIN0/FTM0_FLT3_P$21") (pintype "bidirectional"))
      (node (ref "U$6") (pin "P$25") (pinfunction "P$25_P$25") (pintype "bidirectional"))
    )
    (net (code "46") (name "Net-(U$1-PTE17{slash}ADC0_SE5A{slash}SPI0_SCK{slash}UART2_RX{slash}FTM_CLKIN1{slash}LPTMR0_ALT3)") (class "Default")
      (node (ref "U$1") (pin "P$22") (pinfunction "PTE17/ADC0_SE5A/SPI0_SCK/UART2_RX/FTM_CLKIN1/LPTMR0_ALT3_P$22") (pintype "bidirectional"))
      (node (ref "U$6") (pin "P$27") (pinfunction "P$27_P$27") (pintype "bidirectional"))
    )
    (net (code "47") (name "Net-(U$1-PTE18{slash}ADC0_SE6A{slash}SPI0_SOUT{slash}~{UART2_CTS}{slash}I2C0_SDA)") (class "Default")
      (node (ref "U$1") (pin "P$23") (pinfunction "PTE18/ADC0_SE6A/SPI0_SOUT/~{UART2_CTS}/I2C0_SDA_P$23") (pintype "bidirectional"))
      (node (ref "U$6") (pin "P$29") (pinfunction "P$29_P$29") (pintype "bidirectional"))
    )
    (net (code "48") (name "Net-(U$1-PTE19{slash}ADC0_SE7A{slash}SPI0_SIN{slash}~{UART2_RTS}{slash}I2C0_SCL)") (class "Default")
      (node (ref "U$1") (pin "P$24") (pinfunction "PTE19/ADC0_SE7A/SPI0_SIN/~{UART2_RTS}/I2C0_SCL_P$24") (pintype "bidirectional"))
      (node (ref "U$6") (pin "P$31") (pinfunction "P$31_P$31") (pintype "bidirectional"))
    )
    (net (code "49") (name "Net-(U$1-TAMPER0{slash}~{RTC_WAKEUP})") (class "Default")
      (node (ref "R1") (pin "2") (pinfunction "2_2") (pintype "passive"))
      (node (ref "U$1") (pin "P$29") (pinfunction "TAMPER0/~{RTC_WAKEUP}_P$29") (pintype "bidirectional"))
    )
    (net (code "50") (name "Net-(U$1-VDD_IF)") (class "Default")
      (node (ref "C5") (pin "1") (pinfunction "1_1") (pintype "passive"))
      (node (ref "C6") (pin "1") (pinfunction "1_1") (pintype "passive"))
      (node (ref "C7") (pin "1") (pinfunction "1_1") (pintype "passive"))
      (node (ref "U$1") (pin "P$52") (pinfunction "VDD_PA_P$52") (pintype "bidirectional"))
      (node (ref "U$1") (pin "P$53") (pinfunction "VDD_IF_P$53") (pintype "bidirectional"))
      (node (ref "U$1") (pin "P$54") (pinfunction "VDD_RF_P$54") (pintype "bidirectional"))
    )
    (net (code "51") (name "Net-(U$1-XTAL32)") (class "Default")
      (node (ref "C4") (pin "1") (pinfunction "1_1") (pintype "passive"))
      (node (ref "U$1") (pin "P$30") (pinfunction "XTAL32_P$30") (pintype "bidirectional"))
      (node (ref "U$7") (pin "P$2") (pinfunction "2_P$2") (pintype "passive"))
    )
    (net (code "52") (name "Net-(U$1-XTAL_32M)") (class "Default")
      (node (ref "C1") (pin "1") (pinfunction "1_1") (pintype "passive"))
      (node (ref "U$1") (pin "P$56") (pinfunction "XTAL_32M_P$56") (pintype "bidirectional"))
      (node (ref "U$2") (pin "P$3") (pinfunction "P$3_P$3") (pintype "passive"))
    )
    (net (code "53") (name "Net-(U$1-~{RESET})") (class "Default")
      (node (ref "U$1") (pin "P$41") (pinfunction "~{RESET}_P$41") (pintype "bidirectional"))
      (node (ref "U$6") (pin "P$2") (pinfunction "P$2_P$2") (pintype "bidirectional"))
    )
    (net (code "54") (name "unconnected-(R$23-2-PadP$2)") (class "Default")
      (node (ref "R$23") (pin "P$2") (pinfunction "2_P$2") (pintype "passive"))
    )
    (net (code "55") (name "unconnected-(U$1-ANT_B-PadP$45)") (class "Default")
      (node (ref "U$1") (pin "P$45") (pinfunction "ANT_B_P$45") (pintype "bidirectional"))
    )
    (net (code "56") (name "unconnected-(U$1-GPIO1-PadP$2)") (class "Default")
      (node (ref "U$1") (pin "P$2") (pinfunction "GPIO1_P$2") (pintype "bidirectional"))
    )
    (net (code "57") (name "unconnected-(U$1-GPIO2-PadP$3)") (class "Default")
      (node (ref "U$1") (pin "P$3") (pinfunction "GPIO2_P$3") (pintype "bidirectional"))
    )
    (net (code "58") (name "unconnected-(U$1-NC_57-PadP$57)") (class "Default")
      (node (ref "U$1") (pin "P$57") (pinfunction "NC_57_P$57") (pintype "bidirectional"))
    )
    (net (code "59") (name "unconnected-(U$1-NC_58-PadP$58)") (class "Default")
      (node (ref "U$1") (pin "P$58") (pinfunction "NC_58_P$58") (pintype "bidirectional"))
    )
    (net (code "60") (name "unconnected-(U$1-NC_59-PadP$59)") (class "Default")
      (node (ref "U$1") (pin "P$59") (pinfunction "NC_59_P$59") (pintype "bidirectional"))
    )
    (net (code "61") (name "unconnected-(U$1-NC_60-PadP$60)") (class "Default")
      (node (ref "U$1") (pin "P$60") (pinfunction "NC_60_P$60") (pintype "bidirectional"))
    )
    (net (code "62") (name "unconnected-(U$1-NC_61-PadP$61)") (class "Default")
      (node (ref "U$1") (pin "P$61") (pinfunction "NC_61_P$61") (pintype "bidirectional"))
    )
    (net (code "63") (name "unconnected-(U$1-NC_62-PadP$62)") (class "Default")
      (node (ref "U$1") (pin "P$62") (pinfunction "NC_62_P$62") (pintype "bidirectional"))
    )
    (net (code "64") (name "unconnected-(U$3-CT-PadP$4)") (class "Default")
      (node (ref "U$3") (pin "P$4") (pinfunction "CT_P$4") (pintype "bidirectional"))
    )
    (net (code "65") (name "unconnected-(U$3-N{slash}C-PadP$11)") (class "Default")
      (node (ref "U$3") (pin "P$11") (pinfunction "N/C_P$11") (pintype "bidirectional"))
    )
    (net (code "66") (name "unconnected-(U$3-N{slash}C1-PadP$21)") (class "Default")
      (node (ref "U$3") (pin "P$21") (pinfunction "N/C1_P$21") (pintype "bidirectional"))
    )
    (net (code "67") (name "unconnected-(U$3-PadP$25)") (class "Default")
      (node (ref "U$3") (pin "P$25") (pinfunction "P$25_P$25") (pintype "bidirectional"))
    )
    (net (code "68") (name "unconnected-(U$6-PadP$18)") (class "Default")
      (node (ref "U$6") (pin "P$18") (pinfunction "P$18_P$18") (pintype "bidirectional"))
    )
    (net (code "69") (name "unconnected-(U$6-PadP$20)") (class "Default")
      (node (ref "U$6") (pin "P$20") (pinfunction "P$20_P$20") (pintype "bidirectional"))
    )
    (net (code "70") (name "unconnected-(U$6-PadP$22)") (class "Default")
      (node (ref "U$6") (pin "P$22") (pinfunction "P$22_P$22") (pintype "bidirectional"))
    )
    (net (code "71") (name "unconnected-(U$6-PadP$24)") (class "Default")
      (node (ref "U$6") (pin "P$24") (pinfunction "P$24_P$24") (pintype "bidirectional"))
    )
    (net (code "72") (name "unconnected-(U$6-PadP$26)") (class "Default")
      (node (ref "U$6") (pin "P$26") (pinfunction "P$26_P$26") (pintype "bidirectional"))
    )
    (net (code "73") (name "unconnected-(U$6-PadP$28)") (class "Default")
      (node (ref "U$6") (pin "P$28") (pinfunction "P$28_P$28") (pintype "bidirectional"))
    )
    (net (code "74") (name "unconnected-(U$6-PadP$30)") (class "Default")
      (node (ref "U$6") (pin "P$30") (pinfunction "P$30_P$30") (pintype "bidirectional"))
    )
    (net (code "75") (name "unconnected-(U$6-PadP$32)") (class "Default")
      (node (ref "U$6") (pin "P$32") (pinfunction "P$32_P$32") (pintype "bidirectional"))
    )
    (net (code "76") (name "unconnected-(U$6-PadP$33)") (class "Default")
      (node (ref "U$6") (pin "P$33") (pinfunction "P$33_P$33") (pintype "bidirectional"))
    )
    (net (code "77") (name "unconnected-(U$6-PadP$34)") (class "Default")
      (node (ref "U$6") (pin "P$34") (pinfunction "P$34_P$34") (pintype "bidirectional"))
    )
    (net (code "78") (name "unconnected-(U$6-PadP$35)") (class "Default")
      (node (ref "U$6") (pin "P$35") (pinfunction "P$35_P$35") (pintype "bidirectional"))
    )
    (net (code "79") (name "unconnected-(U$6-PadP$36)") (class "Default")
      (node (ref "U$6") (pin "P$36") (pinfunction "P$36_P$36") (pintype "bidirectional"))
    )
    (net (code "80") (name "unconnected-(U$6-PadP$37)") (class "Default")
      (node (ref "U$6") (pin "P$37") (pinfunction "P$37_P$37") (pintype "bidirectional"))
    )
    (net (code "81") (name "unconnected-(U$6-PadP$38)") (class "Default")
      (node (ref "U$6") (pin "P$38") (pinfunction "P$38_P$38") (pintype "bidirectional"))
    )
    (net (code "82") (name "unconnected-(U$6-PadP$39)") (class "Default")
      (node (ref "U$6") (pin "P$39") (pinfunction "P$39_P$39") (pintype "bidirectional"))
    )
    (net (code "83") (name "unconnected-(U$6-PadP$40)") (class "Default")
      (node (ref "U$6") (pin "P$40") (pinfunction "P$40_P$40") (pintype "bidirectional"))
    )
    (net (code "84") (name "unconnected-(U$6-PadP$41)") (class "Default")
      (node (ref "U$6") (pin "P$41") (pinfunction "P$41_P$41") (pintype "bidirectional"))
    )
    (net (code "85") (name "unconnected-(U$6-PadP$42)") (class "Default")
      (node (ref "U$6") (pin "P$42") (pinfunction "P$42_P$42") (pintype "bidirectional"))
    )
  )
)
